# 05_POWER.net
KiCad netlist of a schematic drawn in Altium Designer
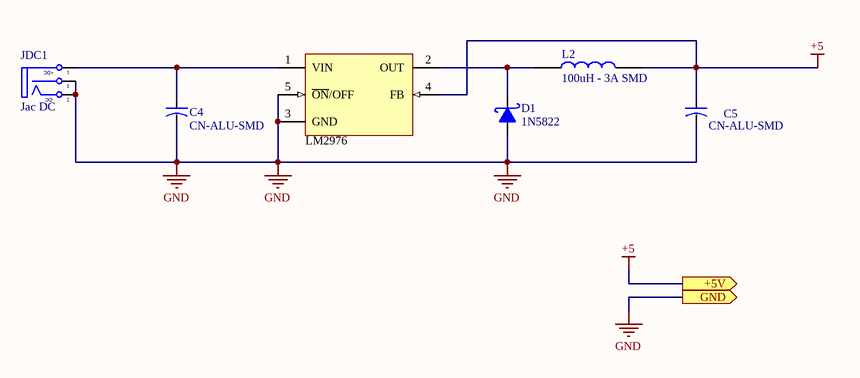
[diagram p0: [05] POWER.SchDoc]

(export (version "E")
  (design (tool "Eeschema 10.0.6"))
  (components
    (comp (ref "C4")
      (value "CN-ALU-SMD")
      (footprint "CAP-ALU-SMD-F")
      (description "Polarized Capacitor (Axial)")
      (fields (field (name "PUBLISHER") "Altium Limited"))
      (libsource (lib "My Library") (part "CAP-ALU-SMD"))
    )
    (comp (ref "C5")
      (value "CN-ALU-SMD")
      (footprint "CAP-ALU-SMD-F")
      (description "Polarized Capacitor (Axial)")
      (fields (field (name "PUBLISHER") "Altium Limited"))
      (libsource (lib "My Library") (part "CAP-ALU-SMD"))
    )
    (comp (ref "D1")
      (value "1N5822")
      (footprint "DIO-SMD-123")
      (description "Schottky Rectifiers")
      (libsource (lib "My Library") (part "1N5822"))
    )
    (comp (ref "JDC1")
      (value "Jac DC")
      (footprint "DC-IN")
      (description "Jac DC input")
      (libsource (lib "My Library") (part "DCIN"))
    )
    (comp (ref "L2")
      (value "100uH - 3A SMD")
      (footprint "Cuon Cam 12x12x10")
      (description "Dán")
      (libsource (lib "Altium_Lib_by_KhueNguyenCreator") (part "CUON CAM 100uH SMD"))
    )
    (comp (ref "U1") (value "LM2976") (footprint "TO263") (libsource (lib "My Library") (part "LM2596")))
  )
  (nets
    (net (code "1") (name "+5") (class "Default")
      (node (ref "C5") (pin "1") (pinfunction "1_1") (pintype "passive"))
      (node (ref "L2") (pin "2") (pinfunction "2_2") (pintype "passive"))
      (node (ref "U1") (pin "4") (pinfunction "FB_4") (pintype "input"))
    )
    (net (code "2") (name "GND") (class "Default")
      (node (ref "C4") (pin "2") (pinfunction "2_2") (pintype "passive"))
      (node (ref "C5") (pin "2") (pinfunction "2_2") (pintype "passive"))
      (node (ref "D1") (pin "1") (pinfunction "A_1") (pintype "passive"))
      (node (ref "JDC1") (pin "2") (pinfunction "TN_2") (pintype "passive"))
      (node (ref "JDC1") (pin "3") (pinfunction "S_3") (pintype "power_in"))
      (node (ref "U1") (pin "3") (pinfunction "GND_3") (pintype "power_in"))
      (node (ref "U1") (pin "5") (pinfunction "~{ON}/OFF_5") (pintype "input"))
    )
    (net (code "3") (name "Net-(D1-K)") (class "Default")
      (node (ref "D1") (pin "2") (pinfunction "K_2") (pintype "passive"))
      (node (ref "L2") (pin "1") (pinfunction "1_1") (pintype "passive"))
      (node (ref "U1") (pin "2") (pinfunction "OUT_2") (pintype "power_in"))
    )
    (net (code "4") (name "Net-(JDC1-T)") (class "Default")
      (node (ref "C4") (pin "1") (pinfunction "1_1") (pintype "passive"))
      (node (ref "JDC1") (pin "1") (pinfunction "T_1") (pintype "passive"))
      (node (ref "U1") (pin "1") (pinfunction "VIN_1") (pintype "power_in"))
    )
  )
)
